# display.net
KiCad netlist of a schematic drawn in EAGLE
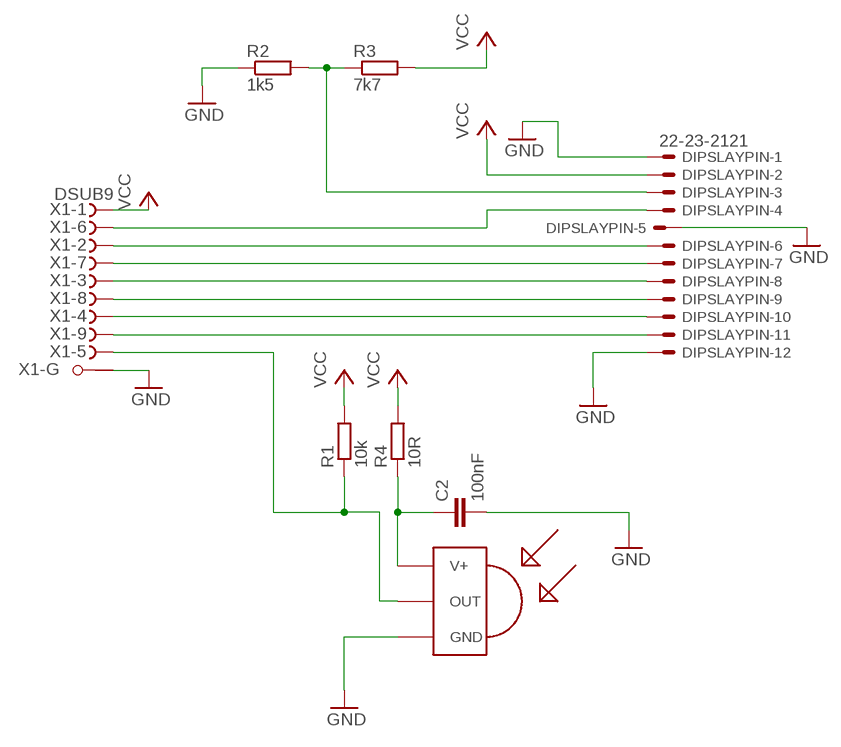
[diagram p0: schematic, sheet 1]

(export (version "E")
  (design (tool "Eeschema 10.0.6"))
  (components
    (comp (ref "C2")
      (value "100nF")
      (footprint "eagle-import:C025-025X050")
      (libsource (lib "eagle-import") (part "C-EU025-025X050"))
    )
    (comp (ref "DIPSLAYPIN")
      (value "22-23-2121")
      (footprint "eagle-import:22-23-2121")
      (fields (field (name "MF") "MOLEX"))
      (libsource (lib "eagle-import") (part "22-23-2121"))
    )
    (comp (ref "R1")
      (value "10k")
      (footprint "eagle-import:0207_10")
      (libsource (lib "eagle-import") (part "R-EU_0207/10"))
    )
    (comp (ref "R2")
      (value "1k5")
      (footprint "eagle-import:0207_10")
      (libsource (lib "eagle-import") (part "R-EU_0207/10"))
    )
    (comp (ref "R3")
      (value "7k7")
      (footprint "eagle-import:0207_10")
      (libsource (lib "eagle-import") (part "R-EU_0207/10"))
    )
    (comp (ref "R4")
      (value "10R")
      (footprint "eagle-import:0207_10")
      (libsource (lib "eagle-import") (part "R-EU_0207/10"))
    )
    (comp (ref "U$1")
      (value "TSOP4838")
      (footprint "eagle-import:TSOP18XX")
      (libsource (lib "eagle-import") (part "TSOP4838"))
    )
    (comp (ref "X1")
      (value "DSUB9")
      (footprint "eagle-import:F09HP")
      (libsource (lib "eagle-import") (part "F09HPS"))
    )
  )
  (nets
    (net (code "1") (name "GND") (class "Default")
      (node (ref "C2") (pin "2") (pinfunction "2_2") (pintype "passive"))
      (node (ref "DIPSLAYPIN") (pin "1") (pinfunction "S_1") (pintype "passive"))
      (node (ref "DIPSLAYPIN") (pin "12") (pinfunction "S_12") (pintype "passive"))
      (node (ref "DIPSLAYPIN") (pin "5") (pinfunction "S_5") (pintype "passive"))
      (node (ref "R2") (pin "1") (pinfunction "1_1") (pintype "passive"))
      (node (ref "U$1") (pin "GND") (pinfunction "GND_GND") (pintype "bidirectional"))
      (node (ref "X1") (pin "G1") (pinfunction "G1_G1") (pintype "passive"))
    )
    (net (code "2") (name "Net-(DIPSLAYPINB-S)") (class "Default")
      (node (ref "DIPSLAYPIN") (pin "10") (pinfunction "S_10") (pintype "passive"))
      (node (ref "X1") (pin "4") (pinfunction "F_4") (pintype "passive"))
    )
    (net (code "3") (name "Net-(DIPSLAYPINC-S)") (class "Default")
      (node (ref "DIPSLAYPIN") (pin "11") (pinfunction "S_11") (pintype "passive"))
      (node (ref "X1") (pin "9") (pinfunction "F_9") (pintype "passive"))
    )
    (net (code "4") (name "Net-(DIPSLAYPINF-S)") (class "Default")
      (node (ref "DIPSLAYPIN") (pin "3") (pinfunction "S_3") (pintype "passive"))
      (node (ref "R2") (pin "2") (pinfunction "2_2") (pintype "passive"))
      (node (ref "R3") (pin "1") (pinfunction "1_1") (pintype "passive"))
    )
    (net (code "5") (name "Net-(DIPSLAYPING-S)") (class "Default")
      (node (ref "DIPSLAYPIN") (pin "4") (pinfunction "S_4") (pintype "passive"))
      (node (ref "X1") (pin "6") (pinfunction "F_6") (pintype "passive"))
    )
    (net (code "6") (name "Net-(DIPSLAYPINI-S)") (class "Default")
      (node (ref "DIPSLAYPIN") (pin "6") (pinfunction "S_6") (pintype "passive"))
      (node (ref "X1") (pin "2") (pinfunction "F_2") (pintype "passive"))
    )
    (net (code "7") (name "Net-(DIPSLAYPINJ-S)") (class "Default")
      (node (ref "DIPSLAYPIN") (pin "7") (pinfunction "S_7") (pintype "passive"))
      (node (ref "X1") (pin "7") (pinfunction "F_7") (pintype "passive"))
    )
    (net (code "8") (name "Net-(DIPSLAYPINK-S)") (class "Default")
      (node (ref "DIPSLAYPIN") (pin "8") (pinfunction "S_8") (pintype "passive"))
      (node (ref "X1") (pin "3") (pinfunction "F_3") (pintype "passive"))
    )
    (net (code "9") (name "Net-(DIPSLAYPINL-S)") (class "Default")
      (node (ref "DIPSLAYPIN") (pin "9") (pinfunction "S_9") (pintype "passive"))
      (node (ref "X1") (pin "8") (pinfunction "F_8") (pintype "passive"))
    )
    (net (code "10") (name "Net-(U$1-V+)") (class "Default")
      (node (ref "C2") (pin "1") (pinfunction "1_1") (pintype "passive"))
      (node (ref "R4") (pin "1") (pinfunction "1_1") (pintype "passive"))
      (node (ref "U$1") (pin "VCC") (pinfunction "V+_VCC") (pintype "bidirectional"))
    )
    (net (code "11") (name "Net-(X1E-F)") (class "Default")
      (node (ref "R1") (pin "1") (pinfunction "1_1") (pintype "passive"))
      (node (ref "U$1") (pin "OUT") (pinfunction "OUT_OUT") (pintype "bidirectional"))
      (node (ref "X1") (pin "5") (pinfunction "F_5") (pintype "passive"))
    )
    (net (code "12") (name "VCC") (class "Default")
      (node (ref "DIPSLAYPIN") (pin "2") (pinfunction "S_2") (pintype "passive"))
      (node (ref "R1") (pin "2") (pinfunction "2_2") (pintype "passive"))
      (node (ref "R3") (pin "2") (pinfunction "2_2") (pintype "passive"))
      (node (ref "R4") (pin "2") (pinfunction "2_2") (pintype "passive"))
      (node (ref "X1") (pin "1") (pinfunction "F_1") (pintype "passive"))
    )
    (net (code "13") (name "unconnected-(X1-PadG2)") (class "Default")
      (node (ref "X1") (pin "G2") (pinfunction "G2_G2") (pintype "passive"))
    )
  )
)
